# Slave.net
KiCad netlist of a schematic drawn in EAGLE
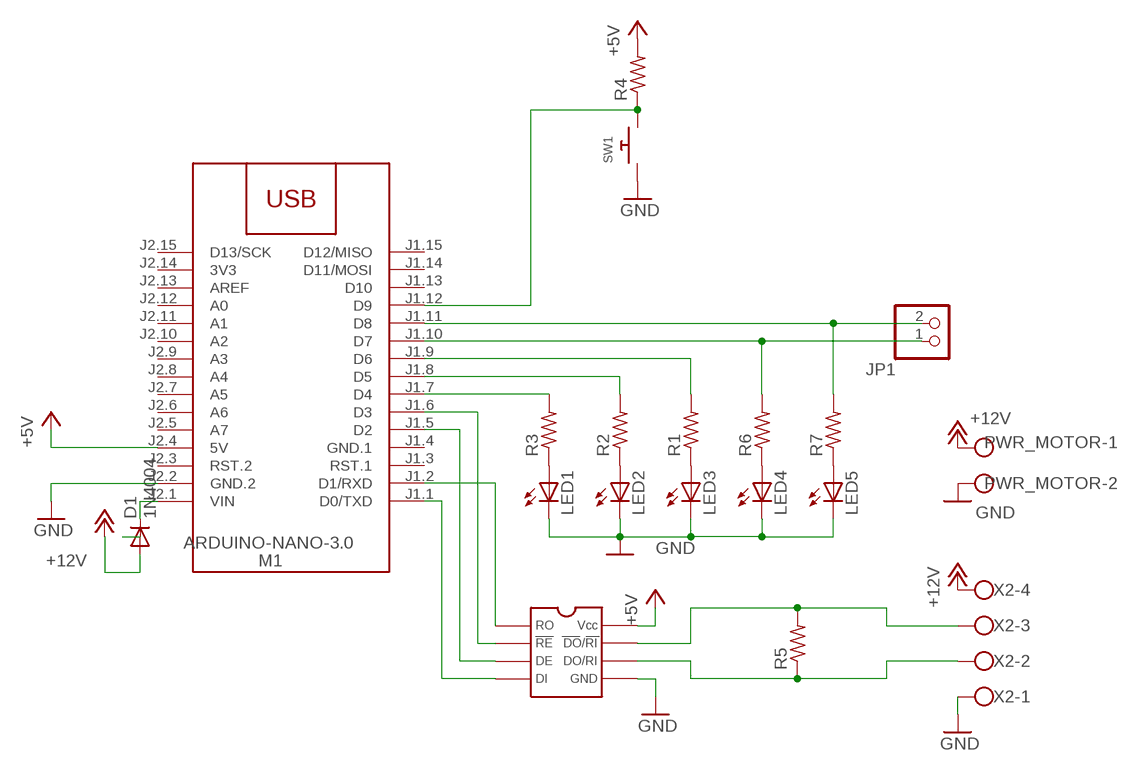
[diagram p0: schematic, sheet 1]

(export (version "E")
  (design (tool "Eeschema 10.0.6"))
  (components
    (comp (ref "D1")
      (value "1N4004")
      (footprint "eagle-import:DO41-10")
      (libsource (lib "eagle-import") (part "1N4004"))
    )
    (comp (ref "JP1")
      (value "PINHD-1X2")
      (footprint "eagle-import:1X02")
      (libsource (lib "eagle-import") (part "PINHD-1X2"))
    )
    (comp (ref "LED1")
      (value "LED5MM")
      (footprint "eagle-import:LED5MM")
      (libsource (lib "eagle-import") (part "LED5MM"))
    )
    (comp (ref "LED2")
      (value "LED5MM")
      (footprint "eagle-import:LED5MM")
      (libsource (lib "eagle-import") (part "LED5MM"))
    )
    (comp (ref "LED3")
      (value "LED5MM")
      (footprint "eagle-import:LED5MM")
      (libsource (lib "eagle-import") (part "LED5MM"))
    )
    (comp (ref "LED4")
      (value "LED5MM")
      (footprint "eagle-import:LED5MM")
      (libsource (lib "eagle-import") (part "LED5MM"))
    )
    (comp (ref "LED5")
      (value "LED5MM")
      (footprint "eagle-import:LED5MM")
      (libsource (lib "eagle-import") (part "LED5MM"))
    )
    (comp (ref "M1")
      (value "ARDUINO-NANO-3.0")
      (footprint "eagle-import:ARDUINO-NANO-3.0")
      (libsource (lib "eagle-import") (part "ARDUINO-NANO-3.0"))
    )
    (comp (ref "PWR_MOTOR")
      (value "W237-102")
      (footprint "eagle-import:W237-102")
      (fields (field (name "MPN") "237-102"))
      (libsource (lib "eagle-import") (part "W237-102"))
    )
    (comp (ref "R1")
      (value "FLIPFLOP-RES")
      (footprint "eagle-import:0805-THM")
      (libsource (lib "eagle-import") (part "FLIPFLOP-RES"))
    )
    (comp (ref "R2")
      (value "FLIPFLOP-RES")
      (footprint "eagle-import:0805-THM")
      (libsource (lib "eagle-import") (part "FLIPFLOP-RES"))
    )
    (comp (ref "R3")
      (value "FLIPFLOP-RES")
      (footprint "eagle-import:0805-THM")
      (libsource (lib "eagle-import") (part "FLIPFLOP-RES"))
    )
    (comp (ref "R4")
      (value "FLIPFLOP-RES")
      (footprint "eagle-import:0805-THM")
      (libsource (lib "eagle-import") (part "FLIPFLOP-RES"))
    )
    (comp (ref "R5")
      (value "FLIPFLOP-RES")
      (footprint "eagle-import:0805-THM")
      (libsource (lib "eagle-import") (part "FLIPFLOP-RES"))
    )
    (comp (ref "R6")
      (value "FLIPFLOP-RES")
      (footprint "eagle-import:0805-THM")
      (libsource (lib "eagle-import") (part "FLIPFLOP-RES"))
    )
    (comp (ref "R7")
      (value "FLIPFLOP-RES")
      (footprint "eagle-import:0805-THM")
      (libsource (lib "eagle-import") (part "FLIPFLOP-RES"))
    )
    (comp (ref "SW1")
      (value "SWITCH_PUSHBUTTONEVQ-PE")
      (footprint "eagle-import:TACT_PANA-EVQ")
      (libsource (lib "eagle-import") (part "SWITCH_PUSHBUTTONEVQ-PE"))
    )
    (comp (ref "U1")
      (value "DS3956N")
      (footprint "eagle-import:DIL08")
      (libsource (lib "eagle-import") (part "DS3956N"))
    )
    (comp (ref "X2")
      (value "W237-4")
      (footprint "eagle-import:W237-4")
      (libsource (lib "eagle-import") (part "W237-4"))
    )
  )
  (nets
    (net (code "1") (name "+5V") (class "Default")
      (node (ref "M1") (pin "J2.4") (pinfunction "5V_J2.4") (pintype "power_in"))
      (node (ref "R4") (pin "2") (pinfunction "2_2") (pintype "passive"))
      (node (ref "U1") (pin "8") (pinfunction "VCC_8") (pintype "bidirectional"))
    )
    (net (code "2") (name "+12V") (class "Default")
      (node (ref "D1") (pin "A") (pinfunction "A_A") (pintype "passive"))
      (node (ref "PWR_MOTOR") (pin "1") (pinfunction "KL_1") (pintype "passive"))
      (node (ref "X2") (pin "4") (pinfunction "KL_4") (pintype "passive"))
    )
    (net (code "3") (name "/3V3") (class "Default")
      (node (ref "M1") (pin "J2.14") (pinfunction "3V3_J2.14") (pintype "power_in"))
    )
    (net (code "4") (name "/GND.1") (class "Default")
      (node (ref "M1") (pin "J1.4") (pinfunction "GND.1_J1.4") (pintype "power_in"))
    )
    (net (code "5") (name "GND") (class "Default")
      (node (ref "LED1") (pin "K") (pinfunction "C_K") (pintype "passive"))
      (node (ref "LED2") (pin "K") (pinfunction "C_K") (pintype "passive"))
      (node (ref "LED3") (pin "K") (pinfunction "C_K") (pintype "passive"))
      (node (ref "LED4") (pin "K") (pinfunction "C_K") (pintype "passive"))
      (node (ref "LED5") (pin "K") (pinfunction "C_K") (pintype "passive"))
      (node (ref "M1") (pin "J2.2") (pinfunction "GND.2_J2.2") (pintype "power_in"))
      (node (ref "PWR_MOTOR") (pin "2") (pinfunction "KL_2") (pintype "passive"))
      (node (ref "SW1") (pin "P$1") (pinfunction "P$1_P$1") (pintype "passive"))
      (node (ref "U1") (pin "5") (pinfunction "GND_5") (pintype "bidirectional"))
      (node (ref "X2") (pin "1") (pinfunction "KL_1") (pintype "passive"))
    )
    (net (code "6") (name "Net-(LED1-PadA)") (class "Default")
      (node (ref "LED1") (pin "A") (pinfunction "A_A") (pintype "passive"))
      (node (ref "R3") (pin "1") (pinfunction "1_1") (pintype "passive"))
    )
    (net (code "7") (name "Net-(LED2-PadA)") (class "Default")
      (node (ref "LED2") (pin "A") (pinfunction "A_A") (pintype "passive"))
      (node (ref "R2") (pin "1") (pinfunction "1_1") (pintype "passive"))
    )
    (net (code "8") (name "Net-(LED3-PadA)") (class "Default")
      (node (ref "LED3") (pin "A") (pinfunction "A_A") (pintype "passive"))
      (node (ref "R1") (pin "1") (pinfunction "1_1") (pintype "passive"))
    )
    (net (code "9") (name "Net-(LED4-PadA)") (class "Default")
      (node (ref "LED4") (pin "A") (pinfunction "A_A") (pintype "passive"))
      (node (ref "R6") (pin "1") (pinfunction "1_1") (pintype "passive"))
    )
    (net (code "10") (name "Net-(LED5-PadA)") (class "Default")
      (node (ref "LED5") (pin "A") (pinfunction "A_A") (pintype "passive"))
      (node (ref "R7") (pin "1") (pinfunction "1_1") (pintype "passive"))
    )
    (net (code "11") (name "Net-(M1-D0{slash}TXD)") (class "Default")
      (node (ref "M1") (pin "J1.1") (pinfunction "D0/TXD_J1.1") (pintype "bidirectional"))
      (node (ref "U1") (pin "4") (pinfunction "DI_4") (pintype "bidirectional"))
    )
    (net (code "12") (name "Net-(M1-D1{slash}RXD)") (class "Default")
      (node (ref "M1") (pin "J1.2") (pinfunction "D1/RXD_J1.2") (pintype "bidirectional"))
      (node (ref "U1") (pin "1") (pinfunction "RO_1") (pintype "bidirectional"))
    )
    (net (code "13") (name "Net-(M1-D2)") (class "Default")
      (node (ref "M1") (pin "J1.5") (pinfunction "D2_J1.5") (pintype "bidirectional"))
      (node (ref "U1") (pin "3") (pinfunction "DE_3") (pintype "bidirectional"))
    )
    (net (code "14") (name "Net-(M1-D3)") (class "Default")
      (node (ref "M1") (pin "J1.6") (pinfunction "D3_J1.6") (pintype "bidirectional"))
      (node (ref "U1") (pin "2") (pinfunction "_RE__2") (pintype "bidirectional"))
    )
    (net (code "15") (name "Net-(M1-D4)") (class "Default")
      (node (ref "M1") (pin "J1.7") (pinfunction "D4_J1.7") (pintype "bidirectional"))
      (node (ref "R3") (pin "2") (pinfunction "2_2") (pintype "passive"))
    )
    (net (code "16") (name "Net-(M1-D5)") (class "Default")
      (node (ref "M1") (pin "J1.8") (pinfunction "D5_J1.8") (pintype "bidirectional"))
      (node (ref "R2") (pin "2") (pinfunction "2_2") (pintype "passive"))
    )
    (net (code "17") (name "Net-(M1-D6)") (class "Default")
      (node (ref "M1") (pin "J1.9") (pinfunction "D6_J1.9") (pintype "bidirectional"))
      (node (ref "R1") (pin "2") (pinfunction "2_2") (pintype "passive"))
    )
    (net (code "18") (name "Net-(M1-D7)") (class "Default")
      (node (ref "JP1") (pin "1") (pinfunction "1_1") (pintype "passive"))
      (node (ref "M1") (pin "J1.10") (pinfunction "D7_J1.10") (pintype "bidirectional"))
      (node (ref "R6") (pin "2") (pinfunction "2_2") (pintype "passive"))
    )
    (net (code "19") (name "Net-(M1-D8)") (class "Default")
      (node (ref "JP1") (pin "2") (pinfunction "2_2") (pintype "passive"))
      (node (ref "M1") (pin "J1.11") (pinfunction "D8_J1.11") (pintype "bidirectional"))
      (node (ref "R7") (pin "2") (pinfunction "2_2") (pintype "passive"))
    )
    (net (code "20") (name "Net-(M1-D9)") (class "Default")
      (node (ref "M1") (pin "J1.12") (pinfunction "D9_J1.12") (pintype "bidirectional"))
      (node (ref "R4") (pin "1") (pinfunction "1_1") (pintype "passive"))
      (node (ref "SW1") (pin "P$2") (pinfunction "P$2_P$2") (pintype "passive"))
    )
    (net (code "21") (name "Net-(M1-VIN)") (class "Default")
      (node (ref "D1") (pin "C") (pinfunction "C_C") (pintype "passive"))
      (node (ref "M1") (pin "J2.1") (pinfunction "VIN_J2.1") (pintype "power_in"))
    )
    (net (code "22") (name "Net-(U1-DO{slash}RI)") (class "Default")
      (node (ref "R5") (pin "1") (pinfunction "1_1") (pintype "passive"))
      (node (ref "U1") (pin "6") (pinfunction "DO/RI_6") (pintype "bidirectional"))
      (node (ref "X2") (pin "2") (pinfunction "KL_2") (pintype "passive"))
    )
    (net (code "23") (name "Net-(U1-_DO{slash}RI_)") (class "Default")
      (node (ref "R5") (pin "2") (pinfunction "2_2") (pintype "passive"))
      (node (ref "U1") (pin "7") (pinfunction "_DO/RI__7") (pintype "bidirectional"))
      (node (ref "X2") (pin "3") (pinfunction "KL_3") (pintype "passive"))
    )
    (net (code "24") (name "unconnected-(M1-A0-PadJ2.12)") (class "Default")
      (node (ref "M1") (pin "J2.12") (pinfunction "A0_J2.12") (pintype "bidirectional"))
    )
    (net (code "25") (name "unconnected-(M1-A1-PadJ2.11)") (class "Default")
      (node (ref "M1") (pin "J2.11") (pinfunction "A1_J2.11") (pintype "bidirectional"))
    )
    (net (code "26") (name "unconnected-(M1-A2-PadJ2.10)") (class "Default")
      (node (ref "M1") (pin "J2.10") (pinfunction "A2_J2.10") (pintype "bidirectional"))
    )
    (net (code "27") (name "unconnected-(M1-A3-PadJ2.9)") (class "Default")
      (node (ref "M1") (pin "J2.9") (pinfunction "A3_J2.9") (pintype "bidirectional"))
    )
    (net (code "28") (name "unconnected-(M1-A4-PadJ2.8)") (class "Default")
      (node (ref "M1") (pin "J2.8") (pinfunction "A4_J2.8") (pintype "bidirectional"))
    )
    (net (code "29") (name "unconnected-(M1-A5-PadJ2.7)") (class "Default")
      (node (ref "M1") (pin "J2.7") (pinfunction "A5_J2.7") (pintype "bidirectional"))
    )
    (net (code "30") (name "unconnected-(M1-A6-PadJ2.6)") (class "Default")
      (node (ref "M1") (pin "J2.6") (pinfunction "A6_J2.6") (pintype "bidirectional"))
    )
    (net (code "31") (name "unconnected-(M1-A7-PadJ2.5)") (class "Default")
      (node (ref "M1") (pin "J2.5") (pinfunction "A7_J2.5") (pintype "bidirectional"))
    )
    (net (code "32") (name "unconnected-(M1-AREF-PadJ2.13)") (class "Default")
      (node (ref "M1") (pin "J2.13") (pinfunction "AREF_J2.13") (pintype "bidirectional"))
    )
    (net (code "33") (name "unconnected-(M1-D10-PadJ1.13)") (class "Default")
      (node (ref "M1") (pin "J1.13") (pinfunction "D10_J1.13") (pintype "bidirectional"))
    )
    (net (code "34") (name "unconnected-(M1-D11{slash}MOSI-PadJ1.14)") (class "Default")
      (node (ref "M1") (pin "J1.14") (pinfunction "D11/MOSI_J1.14") (pintype "bidirectional"))
    )
    (net (code "35") (name "unconnected-(M1-D12{slash}MISO-PadJ1.15)") (class "Default")
      (node (ref "M1") (pin "J1.15") (pinfunction "D12/MISO_J1.15") (pintype "bidirectional"))
    )
    (net (code "36") (name "unconnected-(M1-D13{slash}SCK-PadJ2.15)") (class "Default")
      (node (ref "M1") (pin "J2.15") (pinfunction "D13/SCK_J2.15") (pintype "bidirectional"))
    )
    (net (code "37") (name "unconnected-(M1-RST.1-PadJ1.3)") (class "Default")
      (node (ref "M1") (pin "J1.3") (pinfunction "RST.1_J1.3") (pintype "bidirectional"))
    )
    (net (code "38") (name "unconnected-(M1-RST.2-PadJ2.3)") (class "Default")
      (node (ref "M1") (pin "J2.3") (pinfunction "RST.2_J2.3") (pintype "bidirectional"))
    )
  )
)
